# ext_supply.net
KiCad netlist of a schematic drawn in Altium Designer
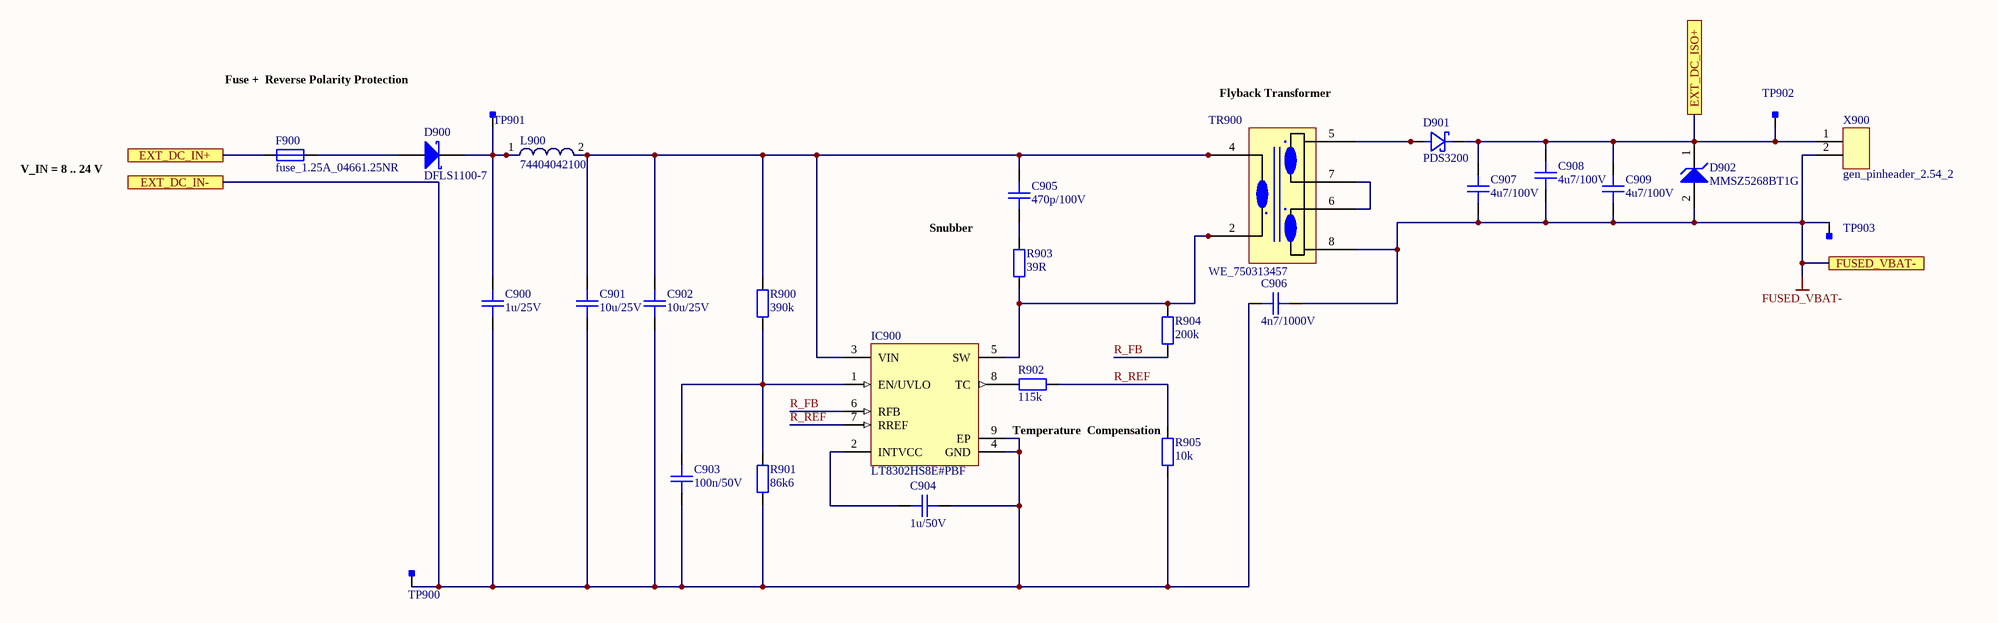
[diagram p0: ext_supply.SchDoc]

(export (version "E")
  (design (tool "Eeschema 10.0.6"))
  (components
    (comp (ref "C900")
      (value "1u/25V")
      (footprint "CAPC2012X14N")
      (description "MLCC")
      (fields (field (name "PART NUMBER") "gen_C_ceramic_1u_25V_X7R_0805"))
      (libsource (lib "OE750") (part "C"))
    )
    (comp (ref "C901")
      (value "10u/25V")
      (footprint "CAPC3225X25N")
      (description "MLCC")
      (fields (field (name "PART NUMBER") "gen_C_ceramic_10u_25V_X7R_1210"))
      (libsource (lib "OE750") (part "C"))
    )
    (comp (ref "C902")
      (value "10u/25V")
      (footprint "CAPC3225X25N")
      (description "MLCC")
      (fields (field (name "PART NUMBER") "gen_C_ceramic_10u_25V_X7R_1210"))
      (libsource (lib "OE750") (part "C"))
    )
    (comp (ref "C903")
      (value "100n/50V")
      (footprint "CAPC1608X08N")
      (description "MLCC")
      (fields (field (name "PART NUMBER") "gen_C_ceramic_100n_50V_X7R_0603"))
      (libsource (lib "OE750") (part "C"))
    )
    (comp (ref "C904")
      (value "1u/50V")
      (footprint "CAPC2012X14N")
      (description "MLCC")
      (fields (field (name "PART NUMBER") "gen_C_ceramic_1u_50V_X7R_0805") (field (name "TOLERANCE") "± 10%"))
      (libsource (lib "OE750") (part "C"))
    )
    (comp (ref "C905")
      (value "470p/100V")
      (footprint "CAPC2012X14N")
      (description "MLCC")
      (fields (field (name "PART NUMBER") "gen_C_ceramic_470p_100V_X7R_0805"))
      (libsource (lib "OE750") (part "C"))
    )
    (comp (ref "C906")
      (value "4n7/1000V")
      (footprint "CAPC4532X16N")
      (description "MLCC")
      (fields (field (name "PART NUMBER") "gen_C_ceramic_4n7_1000V_X7R_1812"))
      (libsource (lib "OE750") (part "C"))
    )
    (comp (ref "C907")
      (value "4u7/100V")
      (footprint "CAPC3216X18N")
      (description "MLCC")
      (fields (field (name "PART NUMBER") "gen_C_ceramic_4u7_100V_X7S_1206"))
      (libsource (lib "OE750") (part "C"))
    )
    (comp (ref "C908")
      (value "4u7/100V")
      (footprint "CAPC3216X18N")
      (description "MLCC")
      (fields (field (name "PART NUMBER") "gen_C_ceramic_4u7_100V_X7S_1206"))
      (libsource (lib "OE750") (part "C"))
    )
    (comp (ref "C909")
      (value "4u7/100V")
      (footprint "CAPC3216X18N")
      (description "MLCC")
      (fields (field (name "PART NUMBER") "gen_C_ceramic_4u7_100V_X7S_1206"))
      (libsource (lib "OE750") (part "C"))
    )
    (comp (ref "D900")
      (value "DFLS1100-7")
      (footprint "DIOD-POWERDI123-2_V")
      (fields (field (name "MANUFACTURER") "Diodes Inc"))
      (libsource (lib "Altium Content Vault") (part "DSKY-AK-2"))
    )
    (comp (ref "D901")
      (value "PDS3200")
      (footprint "PowerDI5")
      (description "Schottky Diode 3A 200V 780mV")
      (fields (field (name "PART NUMBER") "PDS3200-13") (field (name "MANUFACTURER") "DIODES Inc"))
      (libsource (lib "OE750") (part "PDS3200"))
    )
    (comp (ref "D902")
      (value "MMSZ5268BT1G")
      (footprint "ONSC-SOD-123-2-425-04_V")
      (description "Zener Voltage Regulator, 500 mW, 2-Pin SOD-123, Pb-Free, Tape and Reel")
      (fields (field (name "MANUFACTURER") "On Semiconductor"))
      (libsource (lib "Altium Content Vault") (part "ONSC-K1A2-2"))
    )
    (comp (ref "F900")
      (value "fuse_1.25A_04661.25NR")
      (footprint "LITTLEFUSE_466")
      (description "Fuse, Surface Mount, 466 Series, 1.25 A, 63 VAC, 63 VDC, Very Fast Acting, 1206")
      (fields (field (name "MANUFACTURER") "Littlefuse"))
      (libsource (lib "OE750") (part "R_Fuse"))
    )
    (comp (ref "IC900")
      (value "LT8302HS8E#PBF")
      (footprint "LT-S8E-8_V")
      (fields (field (name "PARTNUMBER") "LT8302"))
      (libsource (lib "Altium Content Vault") (part "LT-LT8302-S8E-8"))
    )
    (comp (ref "L900")
      (value "74404042100")
      (footprint "WE-LQS 4018")
      (description "WE-LQS SMD Power Inductor, L=10 µH")
      (fields (field (name "MANUFACTURER") "Wuerth Elektronik"))
      (libsource (lib "Altium Content Vault") (part "WE-IND-INDUCTOR-2"))
    )
    (comp (ref "R900")
      (value "390k")
      (footprint "RESC1608X05N")
      (description "SMD Resistor 390k 0603")
      (fields (field (name "PART NUMBER") "gen_R_390k_0603") (field (name "TOLERANCE") "1%"))
      (libsource (lib "OE750") (part "R"))
    )
    (comp (ref "R901")
      (value "86k6")
      (footprint "RESC1608X05N")
      (description "SMD Resistor 86k6 0603")
      (fields (field (name "PART NUMBER") "gen_R_86k6_0603") (field (name "TOLERANCE") "1%"))
      (libsource (lib "OE750") (part "R"))
    )
    (comp (ref "R902")
      (value "115k")
      (footprint "RESC1608X05N")
      (description "SMD Resistor 115k 0603")
      (fields (field (name "PART NUMBER") "gen_R_115k_0603") (field (name "TOLERANCE") "1%"))
      (libsource (lib "OE750") (part "R"))
    )
    (comp (ref "R903")
      (value "39R")
      (footprint "RESC2012X05N")
      (description "SMD Resistor 39R 0805")
      (fields (field (name "PART NUMBER") "gen_R_39R_0805") (field (name "TOLERANCE") "1%"))
      (libsource (lib "OE750") (part "R"))
    )
    (comp (ref "R904")
      (value "200k")
      (footprint "RESC1608X05N")
      (description "SMD Resistor 200k 0603")
      (fields (field (name "PART NUMBER") "gen_R_200k_0603") (field (name "TOLERANCE") "1%"))
      (libsource (lib "OE750") (part "R"))
    )
    (comp (ref "R905")
      (value "10k")
      (footprint "RESC1608X05N")
      (description "SMD Resistor 10k 0603")
      (fields (field (name "PART NUMBER") "gen_R_10k_0603") (field (name "TOLERANCE") "1%"))
      (libsource (lib "OE750") (part "R"))
    )
    (comp (ref "TP900")
      (value "Testpoint_Square")
      (footprint "Testpoint_S1")
      (description "Testpoint, square")
      (libsource (lib "OE750") (part "Testpoint_Square"))
    )
    (comp (ref "TP901")
      (value "Testpoint_Square")
      (footprint "Testpoint_S1")
      (description "Testpoint, square")
      (libsource (lib "OE750") (part "Testpoint_Square"))
    )
    (comp (ref "TP902")
      (value "Testpoint_Square")
      (footprint "Testpoint_S1")
      (description "Testpoint, square")
      (libsource (lib "OE750") (part "Testpoint_Square"))
    )
    (comp (ref "TP903")
      (value "Testpoint_Square")
      (footprint "Testpoint_S1")
      (description "Testpoint, square")
      (libsource (lib "OE750") (part "Testpoint_Square"))
    )
    (comp (ref "TR900")
      (value "WE_750313457")
      (footprint "WE_750313457")
      (description "MID-FLYLT Flyback Transformers for Linear Technology")
      (fields (field (name "MANUFACTURER") "Würth Elektronik"))
      (libsource (lib "OE750") (part "WE_750313457"))
    )
    (comp (ref "X900")
      (value "gen_pinheader_2.54_2")
      (footprint "Pinheader_2.54_2")
      (description "Standard Pinheader, THD, gerade, 2.54mm")
      (libsource (lib "OE750") (part "X2"))
    )
  )
  (nets
    (net (code "1") (name "/EXT_DC_IN+") (class "Default")
      (node (ref "F900") (pin "1") (pinfunction "1_1") (pintype "passive"))
    )
    (net (code "2") (name "/EXT_DC_IN-") (class "Default")
      (node (ref "C900") (pin "1") (pinfunction "1_1") (pintype "passive"))
      (node (ref "C901") (pin "1") (pinfunction "1_1") (pintype "passive"))
      (node (ref "C902") (pin "1") (pinfunction "1_1") (pintype "passive"))
      (node (ref "C903") (pin "1") (pinfunction "1_1") (pintype "passive"))
      (node (ref "C904") (pin "1") (pinfunction "1_1") (pintype "passive"))
      (node (ref "C906") (pin "1") (pinfunction "1_1") (pintype "passive"))
      (node (ref "IC900") (pin "4") (pinfunction "GND_4") (pintype "power_in"))
      (node (ref "IC900") (pin "9") (pinfunction "EP_9") (pintype "power_in"))
      (node (ref "R901") (pin "1") (pinfunction "1_1") (pintype "passive"))
      (node (ref "R905") (pin "1") (pinfunction "1_1") (pintype "passive"))
      (node (ref "TP900") (pin "1") (pinfunction "1_1") (pintype "passive"))
    )
    (net (code "3") (name "/EXT_DC_ISO+") (class "Default")
      (node (ref "C907") (pin "2") (pinfunction "2_2") (pintype "passive"))
      (node (ref "C908") (pin "2") (pinfunction "2_2") (pintype "passive"))
      (node (ref "C909") (pin "2") (pinfunction "2_2") (pintype "passive"))
      (node (ref "D901") (pin "1") (pinfunction "C_1") (pintype "passive"))
      (node (ref "D902") (pin "1") (pinfunction "K_1") (pintype "passive"))
      (node (ref "TP902") (pin "1") (pinfunction "1_1") (pintype "passive"))
      (node (ref "X900") (pin "1") (pintype "passive"))
    )
    (net (code "4") (name "/R_FB") (class "Default")
      (node (ref "IC900") (pin "6") (pinfunction "RFB_6") (pintype "input"))
      (node (ref "R904") (pin "1") (pinfunction "1_1") (pintype "passive"))
    )
    (net (code "5") (name "/R_REF") (class "Default")
      (node (ref "IC900") (pin "7") (pinfunction "RREF_7") (pintype "input"))
      (node (ref "R902") (pin "2") (pinfunction "2_2") (pintype "passive"))
      (node (ref "R905") (pin "2") (pinfunction "2_2") (pintype "passive"))
    )
    (net (code "6") (name "FUSED_VBAT-") (class "Default")
      (node (ref "C906") (pin "2") (pinfunction "2_2") (pintype "passive"))
      (node (ref "C907") (pin "1") (pinfunction "1_1") (pintype "passive"))
      (node (ref "C908") (pin "1") (pinfunction "1_1") (pintype "passive"))
      (node (ref "C909") (pin "1") (pinfunction "1_1") (pintype "passive"))
      (node (ref "D902") (pin "2") (pinfunction "A_2") (pintype "passive"))
      (node (ref "TP903") (pin "1") (pinfunction "1_1") (pintype "passive"))
      (node (ref "TR900") (pin "8") (pinfunction "8_8") (pintype "passive"))
      (node (ref "X900") (pin "2") (pintype "passive"))
    )
    (net (code "7") (name "Net-(C905-Pad1)") (class "Default")
      (node (ref "C905") (pin "1") (pinfunction "1_1") (pintype "passive"))
      (node (ref "R903") (pin "2") (pinfunction "2_2") (pintype "passive"))
    )
    (net (code "8") (name "Net-(D900-A)") (class "Default")
      (node (ref "D900") (pin "1") (pinfunction "A_1") (pintype "passive"))
      (node (ref "F900") (pin "2") (pinfunction "2_2") (pintype "passive"))
    )
    (net (code "9") (name "Net-(D900-K)") (class "Default")
      (node (ref "C900") (pin "2") (pinfunction "2_2") (pintype "passive"))
      (node (ref "D900") (pin "2") (pinfunction "K_2") (pintype "passive"))
      (node (ref "L900") (pin "1") (pinfunction "1_1") (pintype "passive"))
      (node (ref "TP901") (pin "1") (pinfunction "1_1") (pintype "passive"))
    )
    (net (code "10") (name "Net-(D901-A-Pad2)") (class "Default")
      (node (ref "D901") (pin "2") (pinfunction "A_2") (pintype "passive"))
      (node (ref "D901") (pin "3") (pinfunction "A_3") (pintype "passive"))
      (node (ref "TR900") (pin "5") (pinfunction "5_5") (pintype "passive"))
    )
    (net (code "11") (name "Net-(IC900-EN{slash}UVLO)") (class "Default")
      (node (ref "C903") (pin "2") (pinfunction "2_2") (pintype "passive"))
      (node (ref "IC900") (pin "1") (pinfunction "EN/UVLO_1") (pintype "input"))
      (node (ref "R900") (pin "1") (pinfunction "1_1") (pintype "passive"))
      (node (ref "R901") (pin "2") (pinfunction "2_2") (pintype "passive"))
    )
    (net (code "12") (name "Net-(IC900-INTVCC)") (class "Default")
      (node (ref "C904") (pin "2") (pinfunction "2_2") (pintype "passive"))
      (node (ref "IC900") (pin "2") (pinfunction "INTVCC_2") (pintype "power_in"))
    )
    (net (code "13") (name "Net-(IC900-SW)") (class "Default")
      (node (ref "IC900") (pin "5") (pinfunction "SW_5") (pintype "power_in"))
      (node (ref "R903") (pin "1") (pinfunction "1_1") (pintype "passive"))
      (node (ref "R904") (pin "2") (pinfunction "2_2") (pintype "passive"))
      (node (ref "TR900") (pin "1") (pinfunction "1_1") (pintype "passive"))
      (node (ref "TR900") (pin "2") (pinfunction "2_2") (pintype "passive"))
    )
    (net (code "14") (name "Net-(IC900-TC)") (class "Default")
      (node (ref "IC900") (pin "8") (pinfunction "TC_8") (pintype "output"))
      (node (ref "R902") (pin "1") (pinfunction "1_1") (pintype "passive"))
    )
    (net (code "15") (name "Net-(IC900-VIN)") (class "Default")
      (node (ref "C901") (pin "2") (pinfunction "2_2") (pintype "passive"))
      (node (ref "C902") (pin "2") (pinfunction "2_2") (pintype "passive"))
      (node (ref "C905") (pin "2") (pinfunction "2_2") (pintype "passive"))
      (node (ref "IC900") (pin "3") (pinfunction "VIN_3") (pintype "power_in"))
      (node (ref "L900") (pin "2") (pinfunction "2_2") (pintype "passive"))
      (node (ref "R900") (pin "2") (pinfunction "2_2") (pintype "passive"))
      (node (ref "TR900") (pin "3") (pinfunction "3_3") (pintype "passive"))
      (node (ref "TR900") (pin "4") (pinfunction "4_4") (pintype "passive"))
    )
    (net (code "16") (name "Net-(TR900-Pad6)") (class "Default")
      (node (ref "TR900") (pin "6") (pinfunction "6_6") (pintype "passive"))
      (node (ref "TR900") (pin "7") (pinfunction "7_7") (pintype "passive"))
    )
  )
)
